# 21_GPIOs_EXP.net
KiCad netlist of a schematic drawn in Altium Designer
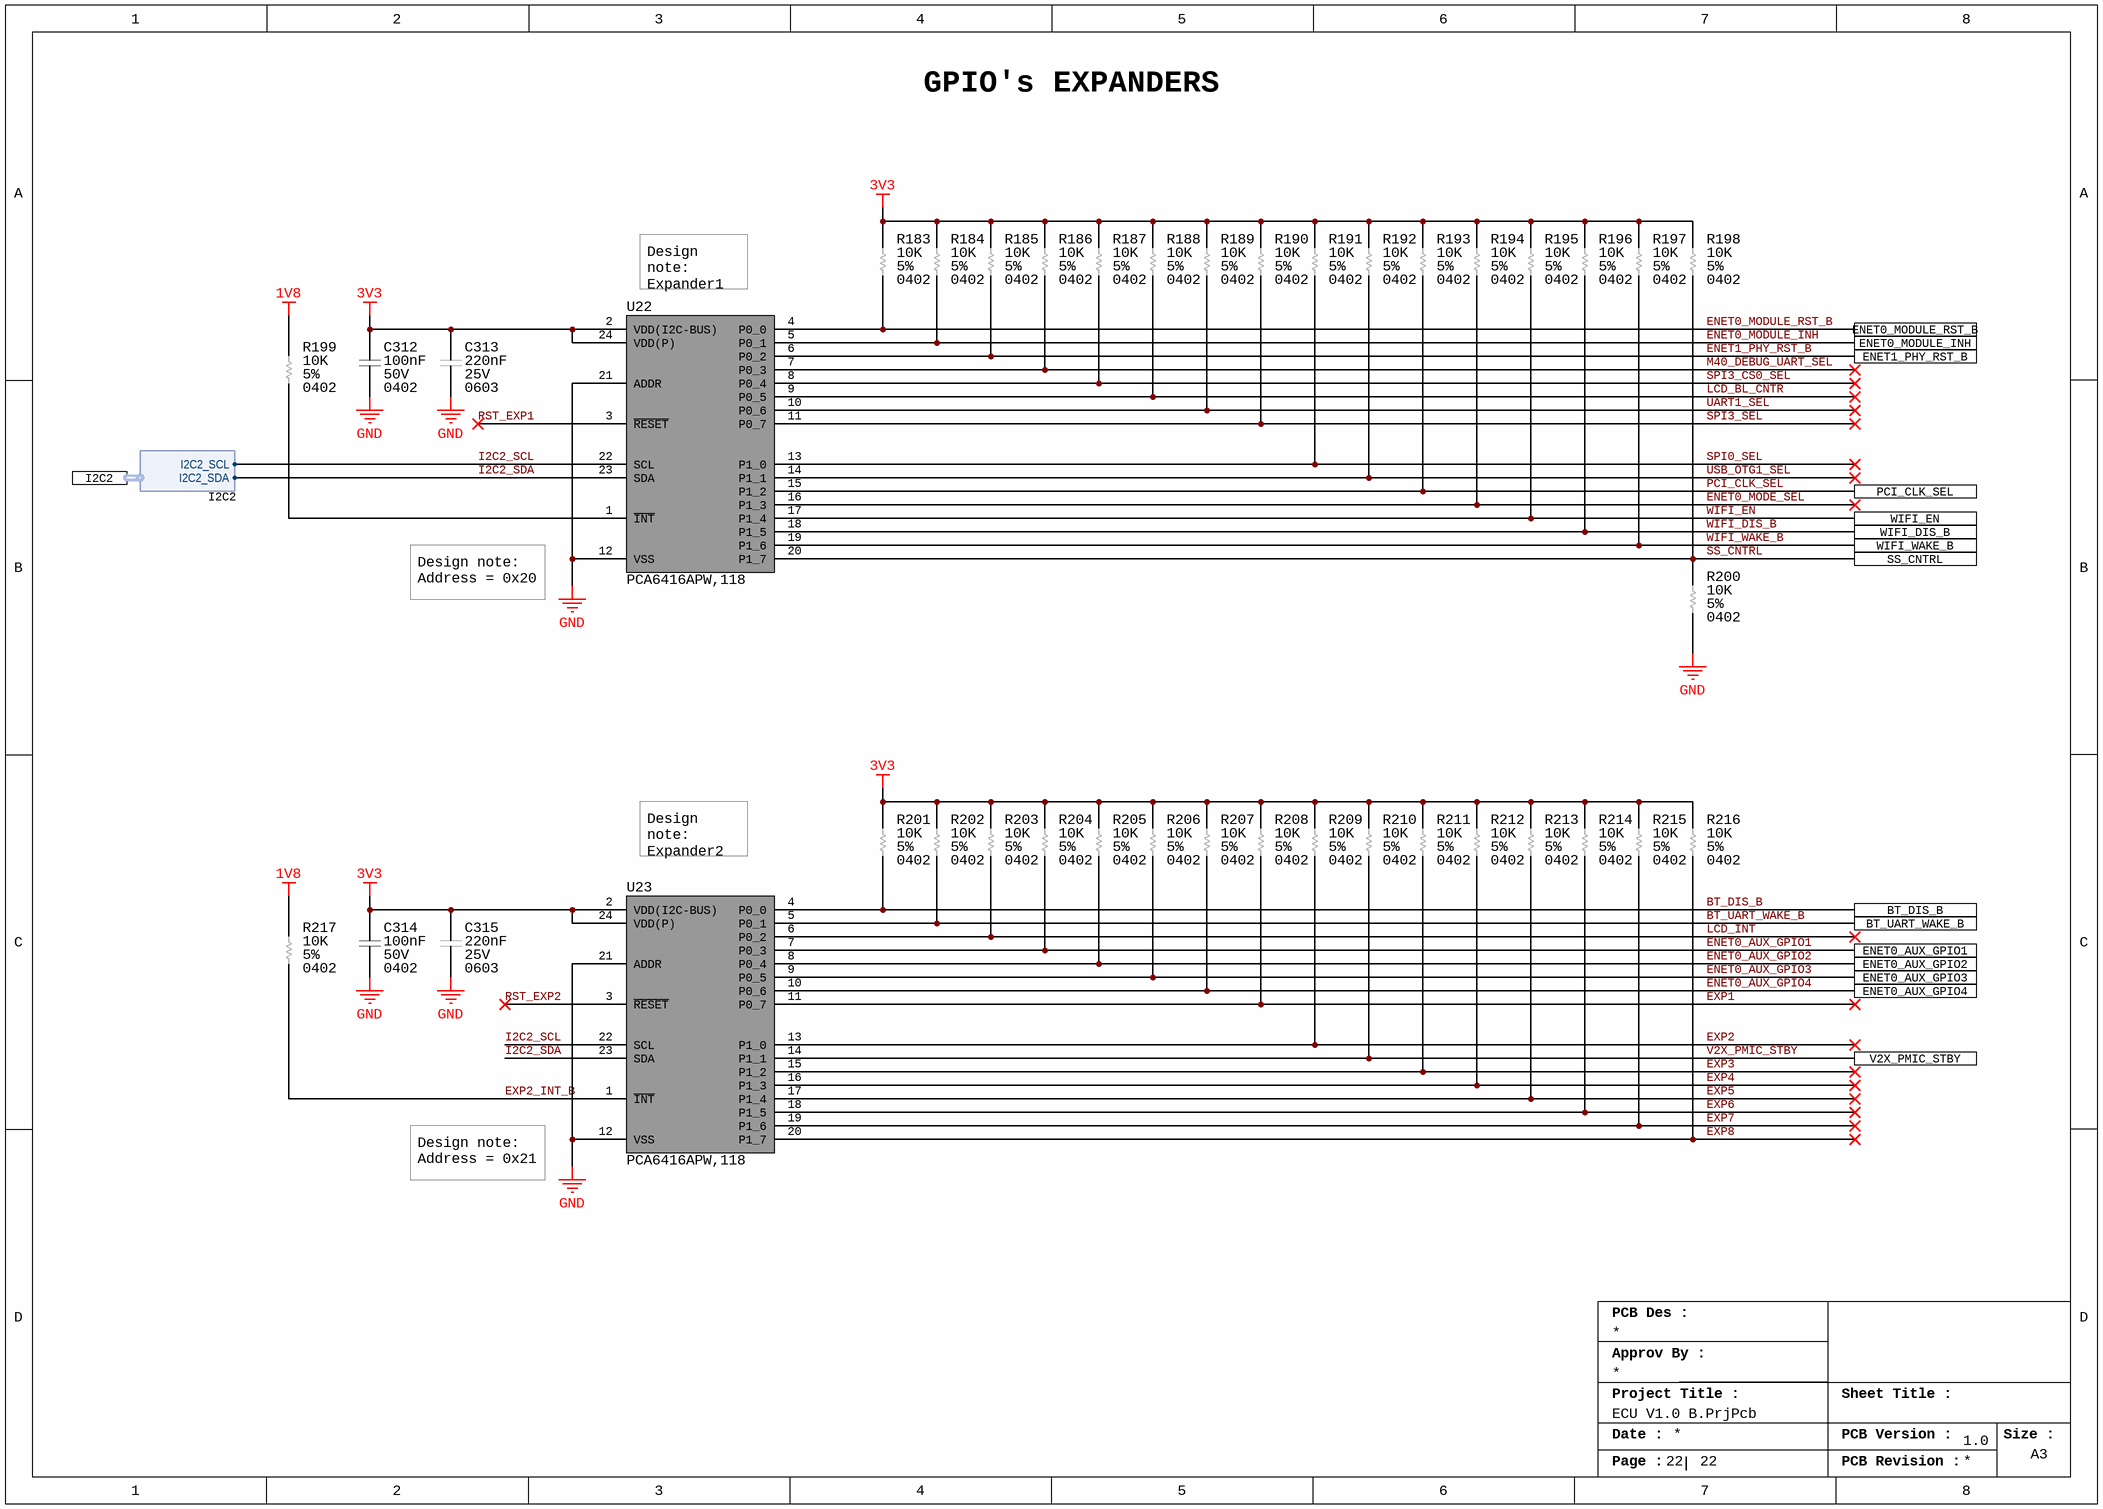
[diagram p0: 21_GPIOs_EXP.SchDoc]

(export (version "E")
  (design (tool "Eeschema 10.0.6"))
  (components
    (comp (ref "C312")
      (value "GRM155R71H104KE14D")
      (footprint "CAP_0402_CAPC1005X05N")
      (description "Multilayer Ceramic Capacitor, 0.1 uF, 16 V, ± 10%, X7R, 0402 [1005 Metric]")
      (fields
        (field (name "MANUFACTURER") "Murata")
        (field (name "TOLERANCE") "10%")
        (field (name "VOLTAGE RATING") "50V")
        (field (name "CAPACITANCE") "100nF")
        (field (name "CASE/PACKAGE") "0402")
      )
      (libsource (lib "Electronic Devices_LIB") (part "CAP_100NF_50V_X7R_0402"))
    )
    (comp (ref "C313")
      (value "GRM188R71E224KA88D")
      (footprint "CAP_0603_CAPC1608X08N")
      (description "Multilayer Ceramic Capacitor, 0.22 uF, 25 V, ± 10%, X7R, 0603 [1608 Metric]")
      (fields
        (field (name "MANUFACTURER") "Murata")
        (field (name "TOLERANCE") "10%")
        (field (name "CASE/PACKAGE") "0603")
        (field (name "VOLTAGE RATING") "25V")
        (field (name "CAPACITANCE") "220nF")
      )
      (libsource (lib "Electronic Devices_LIB") (part "CAP_0.22uF_25V_X7R_0603"))
    )
    (comp (ref "C314")
      (value "GRM155R71H104KE14D")
      (footprint "CAP_0402_CAPC1005X05N")
      (description "Multilayer Ceramic Capacitor, 0.1 uF, 16 V, ± 10%, X7R, 0402 [1005 Metric]")
      (fields
        (field (name "MANUFACTURER") "Murata")
        (field (name "TOLERANCE") "10%")
        (field (name "VOLTAGE RATING") "50V")
        (field (name "CAPACITANCE") "100nF")
        (field (name "CASE/PACKAGE") "0402")
      )
      (libsource (lib "Electronic Devices_LIB") (part "CAP_100NF_50V_X7R_0402"))
    )
    (comp (ref "C315")
      (value "GRM188R71E224KA88D")
      (footprint "CAP_0603_CAPC1608X08N")
      (description "Multilayer Ceramic Capacitor, 0.22 uF, 25 V, ± 10%, X7R, 0603 [1608 Metric]")
      (fields
        (field (name "MANUFACTURER") "Murata")
        (field (name "TOLERANCE") "10%")
        (field (name "CASE/PACKAGE") "0603")
        (field (name "VOLTAGE RATING") "25V")
        (field (name "CAPACITANCE") "220nF")
      )
      (libsource (lib "Electronic Devices_LIB") (part "CAP_0.22uF_25V_X7R_0603"))
    )
    (comp (ref "R183")
      (value "ERJ-2GEJ103X")
      (footprint "RES_0402_RESC1005X04N")
      (description "Res Thick Film 0402 10K Ohm 5% 1/10W ±200ppm/°C Molded SMD Punched Carrier T/R")
      (fields
        (field (name "MANUFACTURER") "Panasonic")
        (field (name "TOLERANCE") "5%")
        (field (name "RESISTANCE") "10K")
        (field (name "CASE/PACKAGE") "0402")
      )
      (libsource (lib "Electronic Devices_LIB") (part "RES_10K_5%_100mW_0402"))
    )
    (comp (ref "R184")
      (value "ERJ-2GEJ103X")
      (footprint "RES_0402_RESC1005X04N")
      (description "Res Thick Film 0402 10K Ohm 5% 1/10W ±200ppm/°C Molded SMD Punched Carrier T/R")
      (fields
        (field (name "MANUFACTURER") "Panasonic")
        (field (name "TOLERANCE") "5%")
        (field (name "RESISTANCE") "10K")
        (field (name "CASE/PACKAGE") "0402")
      )
      (libsource (lib "Electronic Devices_LIB") (part "RES_10K_5%_100mW_0402"))
    )
    (comp (ref "R185")
      (value "ERJ-2GEJ103X")
      (footprint "RES_0402_RESC1005X04N")
      (description "Res Thick Film 0402 10K Ohm 5% 1/10W ±200ppm/°C Molded SMD Punched Carrier T/R")
      (fields
        (field (name "MANUFACTURER") "Panasonic")
        (field (name "TOLERANCE") "5%")
        (field (name "RESISTANCE") "10K")
        (field (name "CASE/PACKAGE") "0402")
      )
      (libsource (lib "Electronic Devices_LIB") (part "RES_10K_5%_100mW_0402"))
    )
    (comp (ref "R186")
      (value "ERJ-2GEJ103X")
      (footprint "RES_0402_RESC1005X04N")
      (description "Res Thick Film 0402 10K Ohm 5% 1/10W ±200ppm/°C Molded SMD Punched Carrier T/R")
      (fields
        (field (name "MANUFACTURER") "Panasonic")
        (field (name "TOLERANCE") "5%")
        (field (name "RESISTANCE") "10K")
        (field (name "CASE/PACKAGE") "0402")
      )
      (libsource (lib "Electronic Devices_LIB") (part "RES_10K_5%_100mW_0402"))
    )
    (comp (ref "R187")
      (value "ERJ-2GEJ103X")
      (footprint "RES_0402_RESC1005X04N")
      (description "Res Thick Film 0402 10K Ohm 5% 1/10W ±200ppm/°C Molded SMD Punched Carrier T/R")
      (fields
        (field (name "MANUFACTURER") "Panasonic")
        (field (name "TOLERANCE") "5%")
        (field (name "RESISTANCE") "10K")
        (field (name "CASE/PACKAGE") "0402")
      )
      (libsource (lib "Electronic Devices_LIB") (part "RES_10K_5%_100mW_0402"))
    )
    (comp (ref "R188")
      (value "ERJ-2GEJ103X")
      (footprint "RES_0402_RESC1005X04N")
      (description "Res Thick Film 0402 10K Ohm 5% 1/10W ±200ppm/°C Molded SMD Punched Carrier T/R")
      (fields
        (field (name "MANUFACTURER") "Panasonic")
        (field (name "TOLERANCE") "5%")
        (field (name "RESISTANCE") "10K")
        (field (name "CASE/PACKAGE") "0402")
      )
      (libsource (lib "Electronic Devices_LIB") (part "RES_10K_5%_100mW_0402"))
    )
    (comp (ref "R189")
      (value "ERJ-2GEJ103X")
      (footprint "RES_0402_RESC1005X04N")
      (description "Res Thick Film 0402 10K Ohm 5% 1/10W ±200ppm/°C Molded SMD Punched Carrier T/R")
      (fields
        (field (name "MANUFACTURER") "Panasonic")
        (field (name "TOLERANCE") "5%")
        (field (name "RESISTANCE") "10K")
        (field (name "CASE/PACKAGE") "0402")
      )
      (libsource (lib "Electronic Devices_LIB") (part "RES_10K_5%_100mW_0402"))
    )
    (comp (ref "R190")
      (value "ERJ-2GEJ103X")
      (footprint "RES_0402_RESC1005X04N")
      (description "Res Thick Film 0402 10K Ohm 5% 1/10W ±200ppm/°C Molded SMD Punched Carrier T/R")
      (fields
        (field (name "MANUFACTURER") "Panasonic")
        (field (name "TOLERANCE") "5%")
        (field (name "RESISTANCE") "10K")
        (field (name "CASE/PACKAGE") "0402")
      )
      (libsource (lib "Electronic Devices_LIB") (part "RES_10K_5%_100mW_0402"))
    )
    (comp (ref "R191")
      (value "ERJ-2GEJ103X")
      (footprint "RES_0402_RESC1005X04N")
      (description "Res Thick Film 0402 10K Ohm 5% 1/10W ±200ppm/°C Molded SMD Punched Carrier T/R")
      (fields
        (field (name "MANUFACTURER") "Panasonic")
        (field (name "TOLERANCE") "5%")
        (field (name "RESISTANCE") "10K")
        (field (name "CASE/PACKAGE") "0402")
      )
      (libsource (lib "Electronic Devices_LIB") (part "RES_10K_5%_100mW_0402"))
    )
    (comp (ref "R192")
      (value "ERJ-2GEJ103X")
      (footprint "RES_0402_RESC1005X04N")
      (description "Res Thick Film 0402 10K Ohm 5% 1/10W ±200ppm/°C Molded SMD Punched Carrier T/R")
      (fields
        (field (name "MANUFACTURER") "Panasonic")
        (field (name "TOLERANCE") "5%")
        (field (name "RESISTANCE") "10K")
        (field (name "CASE/PACKAGE") "0402")
      )
      (libsource (lib "Electronic Devices_LIB") (part "RES_10K_5%_100mW_0402"))
    )
    (comp (ref "R193")
      (value "ERJ-2GEJ103X")
      (footprint "RES_0402_RESC1005X04N")
      (description "Res Thick Film 0402 10K Ohm 5% 1/10W ±200ppm/°C Molded SMD Punched Carrier T/R")
      (fields
        (field (name "MANUFACTURER") "Panasonic")
        (field (name "TOLERANCE") "5%")
        (field (name "RESISTANCE") "10K")
        (field (name "CASE/PACKAGE") "0402")
      )
      (libsource (lib "Electronic Devices_LIB") (part "RES_10K_5%_100mW_0402"))
    )
    (comp (ref "R194")
      (value "ERJ-2GEJ103X")
      (footprint "RES_0402_RESC1005X04N")
      (description "Res Thick Film 0402 10K Ohm 5% 1/10W ±200ppm/°C Molded SMD Punched Carrier T/R")
      (fields
        (field (name "MANUFACTURER") "Panasonic")
        (field (name "TOLERANCE") "5%")
        (field (name "RESISTANCE") "10K")
        (field (name "CASE/PACKAGE") "0402")
      )
      (libsource (lib "Electronic Devices_LIB") (part "RES_10K_5%_100mW_0402"))
    )
    (comp (ref "R195")
      (value "ERJ-2GEJ103X")
      (footprint "RES_0402_RESC1005X04N")
      (description "Res Thick Film 0402 10K Ohm 5% 1/10W ±200ppm/°C Molded SMD Punched Carrier T/R")
      (fields
        (field (name "MANUFACTURER") "Panasonic")
        (field (name "TOLERANCE") "5%")
        (field (name "RESISTANCE") "10K")
        (field (name "CASE/PACKAGE") "0402")
      )
      (libsource (lib "Electronic Devices_LIB") (part "RES_10K_5%_100mW_0402"))
    )
    (comp (ref "R196")
      (value "ERJ-2GEJ103X")
      (footprint "RES_0402_RESC1005X04N")
      (description "Res Thick Film 0402 10K Ohm 5% 1/10W ±200ppm/°C Molded SMD Punched Carrier T/R")
      (fields
        (field (name "MANUFACTURER") "Panasonic")
        (field (name "TOLERANCE") "5%")
        (field (name "RESISTANCE") "10K")
        (field (name "CASE/PACKAGE") "0402")
      )
      (libsource (lib "Electronic Devices_LIB") (part "RES_10K_5%_100mW_0402"))
    )
    (comp (ref "R197")
      (value "ERJ-2GEJ103X")
      (footprint "RES_0402_RESC1005X04N")
      (description "Res Thick Film 0402 10K Ohm 5% 1/10W ±200ppm/°C Molded SMD Punched Carrier T/R")
      (fields
        (field (name "MANUFACTURER") "Panasonic")
        (field (name "TOLERANCE") "5%")
        (field (name "RESISTANCE") "10K")
        (field (name "CASE/PACKAGE") "0402")
      )
      (libsource (lib "Electronic Devices_LIB") (part "RES_10K_5%_100mW_0402"))
    )
    (comp (ref "R198")
      (value "ERJ-2GEJ103X")
      (footprint "RES_0402_RESC1005X04N")
      (description "Res Thick Film 0402 10K Ohm 5% 1/10W ±200ppm/°C Molded SMD Punched Carrier T/R")
      (fields
        (field (name "MANUFACTURER") "Panasonic")
        (field (name "TOLERANCE") "5%")
        (field (name "RESISTANCE") "10K")
        (field (name "CASE/PACKAGE") "0402")
      )
      (libsource (lib "Electronic Devices_LIB") (part "RES_10K_5%_100mW_0402"))
    )
    (comp (ref "R199")
      (value "ERJ-2GEJ103X")
      (footprint "RES_0402_RESC1005X04N")
      (description "Res Thick Film 0402 10K Ohm 5% 1/10W ±200ppm/°C Molded SMD Punched Carrier T/R")
      (fields
        (field (name "MANUFACTURER") "Panasonic")
        (field (name "TOLERANCE") "5%")
        (field (name "RESISTANCE") "10K")
        (field (name "CASE/PACKAGE") "0402")
      )
      (libsource (lib "Electronic Devices_LIB") (part "RES_10K_5%_100mW_0402"))
    )
    (comp (ref "R200")
      (value "ERJ-2GEJ103X")
      (footprint "RES_0402_RESC1005X04N")
      (description "Res Thick Film 0402 10K Ohm 5% 1/10W ±200ppm/°C Molded SMD Punched Carrier T/R")
      (fields
        (field (name "MANUFACTURER") "Panasonic")
        (field (name "TOLERANCE") "5%")
        (field (name "RESISTANCE") "10K")
        (field (name "CASE/PACKAGE") "0402")
      )
      (libsource (lib "Electronic Devices_LIB") (part "RES_10K_5%_100mW_0402"))
    )
    (comp (ref "R201")
      (value "ERJ-2GEJ103X")
      (footprint "RES_0402_RESC1005X04N")
      (description "Res Thick Film 0402 10K Ohm 5% 1/10W ±200ppm/°C Molded SMD Punched Carrier T/R")
      (fields
        (field (name "MANUFACTURER") "Panasonic")
        (field (name "TOLERANCE") "5%")
        (field (name "RESISTANCE") "10K")
        (field (name "CASE/PACKAGE") "0402")
      )
      (libsource (lib "Electronic Devices_LIB") (part "RES_10K_5%_100mW_0402"))
    )
    (comp (ref "R202")
      (value "ERJ-2GEJ103X")
      (footprint "RES_0402_RESC1005X04N")
      (description "Res Thick Film 0402 10K Ohm 5% 1/10W ±200ppm/°C Molded SMD Punched Carrier T/R")
      (fields
        (field (name "MANUFACTURER") "Panasonic")
        (field (name "TOLERANCE") "5%")
        (field (name "RESISTANCE") "10K")
        (field (name "CASE/PACKAGE") "0402")
      )
      (libsource (lib "Electronic Devices_LIB") (part "RES_10K_5%_100mW_0402"))
    )
    (comp (ref "R203")
      (value "ERJ-2GEJ103X")
      (footprint "RES_0402_RESC1005X04N")
      (description "Res Thick Film 0402 10K Ohm 5% 1/10W ±200ppm/°C Molded SMD Punched Carrier T/R")
      (fields
        (field (name "MANUFACTURER") "Panasonic")
        (field (name "TOLERANCE") "5%")
        (field (name "RESISTANCE") "10K")
        (field (name "CASE/PACKAGE") "0402")
      )
      (libsource (lib "Electronic Devices_LIB") (part "RES_10K_5%_100mW_0402"))
    )
    (comp (ref "R204")
      (value "ERJ-2GEJ103X")
      (footprint "RES_0402_RESC1005X04N")
      (description "Res Thick Film 0402 10K Ohm 5% 1/10W ±200ppm/°C Molded SMD Punched Carrier T/R")
      (fields
        (field (name "MANUFACTURER") "Panasonic")
        (field (name "TOLERANCE") "5%")
        (field (name "RESISTANCE") "10K")
        (field (name "CASE/PACKAGE") "0402")
      )
      (libsource (lib "Electronic Devices_LIB") (part "RES_10K_5%_100mW_0402"))
    )
    (comp (ref "R205")
      (value "ERJ-2GEJ103X")
      (footprint "RES_0402_RESC1005X04N")
      (description "Res Thick Film 0402 10K Ohm 5% 1/10W ±200ppm/°C Molded SMD Punched Carrier T/R")
      (fields
        (field (name "MANUFACTURER") "Panasonic")
        (field (name "TOLERANCE") "5%")
        (field (name "RESISTANCE") "10K")
        (field (name "CASE/PACKAGE") "0402")
      )
      (libsource (lib "Electronic Devices_LIB") (part "RES_10K_5%_100mW_0402"))
    )
    (comp (ref "R206")
      (value "ERJ-2GEJ103X")
      (footprint "RES_0402_RESC1005X04N")
      (description "Res Thick Film 0402 10K Ohm 5% 1/10W ±200ppm/°C Molded SMD Punched Carrier T/R")
      (fields
        (field (name "MANUFACTURER") "Panasonic")
        (field (name "TOLERANCE") "5%")
        (field (name "RESISTANCE") "10K")
        (field (name "CASE/PACKAGE") "0402")
      )
      (libsource (lib "Electronic Devices_LIB") (part "RES_10K_5%_100mW_0402"))
    )
    (comp (ref "R207")
      (value "ERJ-2GEJ103X")
      (footprint "RES_0402_RESC1005X04N")
      (description "Res Thick Film 0402 10K Ohm 5% 1/10W ±200ppm/°C Molded SMD Punched Carrier T/R")
      (fields
        (field (name "MANUFACTURER") "Panasonic")
        (field (name "TOLERANCE") "5%")
        (field (name "RESISTANCE") "10K")
        (field (name "CASE/PACKAGE") "0402")
      )
      (libsource (lib "Electronic Devices_LIB") (part "RES_10K_5%_100mW_0402"))
    )
    (comp (ref "R208")
      (value "ERJ-2GEJ103X")
      (footprint "RES_0402_RESC1005X04N")
      (description "Res Thick Film 0402 10K Ohm 5% 1/10W ±200ppm/°C Molded SMD Punched Carrier T/R")
      (fields
        (field (name "MANUFACTURER") "Panasonic")
        (field (name "TOLERANCE") "5%")
        (field (name "RESISTANCE") "10K")
        (field (name "CASE/PACKAGE") "0402")
      )
      (libsource (lib "Electronic Devices_LIB") (part "RES_10K_5%_100mW_0402"))
    )
    (comp (ref "R209")
      (value "ERJ-2GEJ103X")
      (footprint "RES_0402_RESC1005X04N")
      (description "Res Thick Film 0402 10K Ohm 5% 1/10W ±200ppm/°C Molded SMD Punched Carrier T/R")
      (fields
        (field (name "MANUFACTURER") "Panasonic")
        (field (name "TOLERANCE") "5%")
        (field (name "RESISTANCE") "10K")
        (field (name "CASE/PACKAGE") "0402")
      )
      (libsource (lib "Electronic Devices_LIB") (part "RES_10K_5%_100mW_0402"))
    )
    (comp (ref "R210")
      (value "ERJ-2GEJ103X")
      (footprint "RES_0402_RESC1005X04N")
      (description "Res Thick Film 0402 10K Ohm 5% 1/10W ±200ppm/°C Molded SMD Punched Carrier T/R")
      (fields
        (field (name "MANUFACTURER") "Panasonic")
        (field (name "TOLERANCE") "5%")
        (field (name "RESISTANCE") "10K")
        (field (name "CASE/PACKAGE") "0402")
      )
      (libsource (lib "Electronic Devices_LIB") (part "RES_10K_5%_100mW_0402"))
    )
    (comp (ref "R211")
      (value "ERJ-2GEJ103X")
      (footprint "RES_0402_RESC1005X04N")
      (description "Res Thick Film 0402 10K Ohm 5% 1/10W ±200ppm/°C Molded SMD Punched Carrier T/R")
      (fields
        (field (name "MANUFACTURER") "Panasonic")
        (field (name "TOLERANCE") "5%")
        (field (name "RESISTANCE") "10K")
        (field (name "CASE/PACKAGE") "0402")
      )
      (libsource (lib "Electronic Devices_LIB") (part "RES_10K_5%_100mW_0402"))
    )
    (comp (ref "R212")
      (value "ERJ-2GEJ103X")
      (footprint "RES_0402_RESC1005X04N")
      (description "Res Thick Film 0402 10K Ohm 5% 1/10W ±200ppm/°C Molded SMD Punched Carrier T/R")
      (fields
        (field (name "MANUFACTURER") "Panasonic")
        (field (name "TOLERANCE") "5%")
        (field (name "RESISTANCE") "10K")
        (field (name "CASE/PACKAGE") "0402")
      )
      (libsource (lib "Electronic Devices_LIB") (part "RES_10K_5%_100mW_0402"))
    )
    (comp (ref "R213")
      (value "ERJ-2GEJ103X")
      (footprint "RES_0402_RESC1005X04N")
      (description "Res Thick Film 0402 10K Ohm 5% 1/10W ±200ppm/°C Molded SMD Punched Carrier T/R")
      (fields
        (field (name "MANUFACTURER") "Panasonic")
        (field (name "TOLERANCE") "5%")
        (field (name "RESISTANCE") "10K")
        (field (name "CASE/PACKAGE") "0402")
      )
      (libsource (lib "Electronic Devices_LIB") (part "RES_10K_5%_100mW_0402"))
    )
    (comp (ref "R214")
      (value "ERJ-2GEJ103X")
      (footprint "RES_0402_RESC1005X04N")
      (description "Res Thick Film 0402 10K Ohm 5% 1/10W ±200ppm/°C Molded SMD Punched Carrier T/R")
      (fields
        (field (name "MANUFACTURER") "Panasonic")
        (field (name "TOLERANCE") "5%")
        (field (name "RESISTANCE") "10K")
        (field (name "CASE/PACKAGE") "0402")
      )
      (libsource (lib "Electronic Devices_LIB") (part "RES_10K_5%_100mW_0402"))
    )
    (comp (ref "R215")
      (value "ERJ-2GEJ103X")
      (footprint "RES_0402_RESC1005X04N")
      (description "Res Thick Film 0402 10K Ohm 5% 1/10W ±200ppm/°C Molded SMD Punched Carrier T/R")
      (fields
        (field (name "MANUFACTURER") "Panasonic")
        (field (name "TOLERANCE") "5%")
        (field (name "RESISTANCE") "10K")
        (field (name "CASE/PACKAGE") "0402")
      )
      (libsource (lib "Electronic Devices_LIB") (part "RES_10K_5%_100mW_0402"))
    )
    (comp (ref "R216")
      (value "ERJ-2GEJ103X")
      (footprint "RES_0402_RESC1005X04N")
      (description "Res Thick Film 0402 10K Ohm 5% 1/10W ±200ppm/°C Molded SMD Punched Carrier T/R")
      (fields
        (field (name "MANUFACTURER") "Panasonic")
        (field (name "TOLERANCE") "5%")
        (field (name "RESISTANCE") "10K")
        (field (name "CASE/PACKAGE") "0402")
      )
      (libsource (lib "Electronic Devices_LIB") (part "RES_10K_5%_100mW_0402"))
    )
    (comp (ref "R217")
      (value "ERJ-2GEJ103X")
      (footprint "RES_0402_RESC1005X04N")
      (description "Res Thick Film 0402 10K Ohm 5% 1/10W ±200ppm/°C Molded SMD Punched Carrier T/R")
      (fields
        (field (name "MANUFACTURER") "Panasonic")
        (field (name "TOLERANCE") "5%")
        (field (name "RESISTANCE") "10K")
        (field (name "CASE/PACKAGE") "0402")
      )
      (libsource (lib "Electronic Devices_LIB") (part "RES_10K_5%_100mW_0402"))
    )
    (comp (ref "U22")
      (value "PCA6416APW,118")
      (footprint "PCA6416APW118")
      (description "I2C/SMBus Interface 100kHz/400kHz 5.5V 24-Pin TSSOP T/R")
      (fields (field (name "MANUFACTURER") "NXP Semiconductors"))
      (libsource (lib "Electronic Devices_LIB") (part "IC_EXPANDER_16_PCA6416APW,118"))
    )
    (comp (ref "U23")
      (value "PCA6416APW,118")
      (footprint "PCA6416APW118")
      (description "I2C/SMBus Interface 100kHz/400kHz 5.5V 24-Pin TSSOP T/R")
      (fields (field (name "MANUFACTURER") "NXP Semiconductors"))
      (libsource (lib "Electronic Devices_LIB") (part "IC_EXPANDER_16_PCA6416APW,118"))
    )
  )
  (nets
    (net (code "2") (name "/BT_DIS_B") (class "Default")
      (node (ref "R201") (pin "1") (pinfunction "1_1") (pintype "passive"))
      (node (ref "U23") (pin "4") (pinfunction "P0_0_4") (pintype "passive"))
    )
    (net (code "3") (name "/BT_UART_WAKE_B") (class "Default")
      (node (ref "R202") (pin "1") (pinfunction "1_1") (pintype "passive"))
      (node (ref "U23") (pin "5") (pinfunction "P0_1_5") (pintype "passive"))
    )
    (net (code "4") (name "/ENET0_AUX_GPIO1") (class "Default")
      (node (ref "R204") (pin "1") (pinfunction "1_1") (pintype "passive"))
      (node (ref "U23") (pin "7") (pinfunction "P0_3_7") (pintype "passive"))
    )
    (net (code "5") (name "/ENET0_AUX_GPIO2") (class "Default")
      (node (ref "R205") (pin "1") (pinfunction "1_1") (pintype "passive"))
      (node (ref "U23") (pin "8") (pinfunction "P0_4_8") (pintype "passive"))
    )
    (net (code "6") (name "/ENET0_AUX_GPIO3") (class "Default")
      (node (ref "R206") (pin "1") (pinfunction "1_1") (pintype "passive"))
      (node (ref "U23") (pin "9") (pinfunction "P0_5_9") (pintype "passive"))
    )
    (net (code "7") (name "/ENET0_AUX_GPIO4") (class "Default")
      (node (ref "R207") (pin "1") (pinfunction "1_1") (pintype "passive"))
      (node (ref "U23") (pin "10") (pinfunction "P0_6_10") (pintype "passive"))
    )
    (net (code "8") (name "/ENET0_MODE_SEL") (class "Default")
      (node (ref "R194") (pin "1") (pinfunction "1_1") (pintype "passive"))
      (node (ref "U22") (pin "16") (pinfunction "P1_3_16") (pintype "passive"))
    )
    (net (code "9") (name "/ENET0_MODULE_INH") (class "Default")
      (node (ref "R184") (pin "1") (pinfunction "1_1") (pintype "passive"))
      (node (ref "U22") (pin "5") (pinfunction "P0_1_5") (pintype "passive"))
    )
    (net (code "10") (name "/ENET0_MODULE_RST_B") (class "Default")
      (node (ref "R183") (pin "1") (pinfunction "1_1") (pintype "passive"))
      (node (ref "U22") (pin "4") (pinfunction "P0_0_4") (pintype "passive"))
    )
    (net (code "11") (name "/ENET1_PHY_RST_B") (class "Default")
      (node (ref "R185") (pin "1") (pinfunction "1_1") (pintype "passive"))
      (node (ref "U22") (pin "6") (pinfunction "P0_2_6") (pintype "passive"))
    )
    (net (code "12") (name "/EXP1") (class "Default")
      (node (ref "R208") (pin "1") (pinfunction "1_1") (pintype "passive"))
      (node (ref "U23") (pin "11") (pinfunction "P0_7_11") (pintype "passive"))
    )
    (net (code "13") (name "/EXP2") (class "Default")
      (node (ref "R209") (pin "1") (pinfunction "1_1") (pintype "passive"))
      (node (ref "U23") (pin "13") (pinfunction "P1_0_13") (pintype "passive"))
    )
    (net (code "14") (name "/EXP2_INT_B") (class "Default")
      (node (ref "R217") (pin "1") (pinfunction "1_1") (pintype "passive"))
      (node (ref "U23") (pin "1") (pinfunction "~{INT}_1") (pintype "passive"))
    )
    (net (code "15") (name "/EXP3") (class "Default")
      (node (ref "R211") (pin "1") (pinfunction "1_1") (pintype "passive"))
      (node (ref "U23") (pin "15") (pinfunction "P1_2_15") (pintype "passive"))
    )
    (net (code "16") (name "/EXP4") (class "Default")
      (node (ref "R212") (pin "1") (pinfunction "1_1") (pintype "passive"))
      (node (ref "U23") (pin "16") (pinfunction "P1_3_16") (pintype "passive"))
    )
    (net (code "17") (name "/EXP5") (class "Default")
      (node (ref "R213") (pin "1") (pinfunction "1_1") (pintype "passive"))
      (node (ref "U23") (pin "17") (pinfunction "P1_4_17") (pintype "passive"))
    )
    (net (code "18") (name "/EXP6") (class "Default")
      (node (ref "R214") (pin "1") (pinfunction "1_1") (pintype "passive"))
      (node (ref "U23") (pin "18") (pinfunction "P1_5_18") (pintype "passive"))
    )
    (net (code "19") (name "/EXP7") (class "Default")
      (node (ref "R215") (pin "1") (pinfunction "1_1") (pintype "passive"))
      (node (ref "U23") (pin "19") (pinfunction "P1_6_19") (pintype "passive"))
    )
    (net (code "20") (name "/EXP8") (class "Default")
      (node (ref "R216") (pin "1") (pinfunction "1_1") (pintype "passive"))
      (node (ref "U23") (pin "20") (pinfunction "P1_7_20") (pintype "passive"))
    )
    (net (code "21") (name "/I2C2_SCL") (class "Default")
      (node (ref "U22") (pin "22") (pinfunction "SCL_22") (pintype "passive"))
      (node (ref "U23") (pin "22") (pinfunction "SCL_22") (pintype "passive"))
    )
    (net (code "22") (name "/I2C2_SDA") (class "Default")
      (node (ref "U22") (pin "23") (pinfunction "SDA_23") (pintype "passive"))
      (node (ref "U23") (pin "23") (pinfunction "SDA_23") (pintype "passive"))
    )
    (net (code "23") (name "/LCD_BL_CNTR") (class "Default")
      (node (ref "R188") (pin "1") (pinfunction "1_1") (pintype "passive"))
      (node (ref "U22") (pin "9") (pinfunction "P0_5_9") (pintype "passive"))
    )
    (net (code "24") (name "/LCD_INT") (class "Default")
      (node (ref "R203") (pin "1") (pinfunction "1_1") (pintype "passive"))
      (node (ref "U23") (pin "6") (pinfunction "P0_2_6") (pintype "passive"))
    )
    (net (code "25") (name "/M40_DEBUG_UART_SEL") (class "Default")
      (node (ref "R186") (pin "1") (pinfunction "1_1") (pintype "passive"))
      (node (ref "U22") (pin "7") (pinfunction "P0_3_7") (pintype "passive"))
    )
    (net (code "26") (name "/PCI_CLK_SEL") (class "Default")
      (node (ref "R193") (pin "1") (pinfunction "1_1") (pintype "passive"))
      (node (ref "U22") (pin "15") (pinfunction "P1_2_15") (pintype "passive"))
    )
    (net (code "27") (name "/RST_EXP1") (class "Default")
      (node (ref "U22") (pin "3") (pinfunction "~{RESET}_3") (pintype "passive+no_connect"))
    )
    (net (code "28") (name "/RST_EXP2") (class "Default")
      (node (ref "U23") (pin "3") (pinfunction "~{RESET}_3") (pintype "passive+no_connect"))
    )
    (net (code "29") (name "/SPI0_SEL") (class "Default")
      (node (ref "R191") (pin "1") (pinfunction "1_1") (pintype "passive"))
      (node (ref "U22") (pin "13") (pinfunction "P1_0_13") (pintype "passive"))
    )
    (net (code "30") (name "/SPI3_CS0_SEL") (class "Default")
      (node (ref "R187") (pin "1") (pinfunction "1_1") (pintype "passive"))
      (node (ref "U22") (pin "8") (pinfunction "P0_4_8") (pintype "passive"))
    )
    (net (code "31") (name "/SPI3_SEL") (class "Default")
      (node (ref "R190") (pin "1") (pinfunction "1_1") (pintype "passive"))
      (node (ref "U22") (pin "11") (pinfunction "P0_7_11") (pintype "passive"))
    )
    (net (code "32") (name "/SS_CNTRL") (class "Default")
      (node (ref "R198") (pin "1") (pinfunction "1_1") (pintype "passive"))
      (node (ref "R200") (pin "2") (pinfunction "2_2") (pintype "passive"))
      (node (ref "U22") (pin "20") (pinfunction "P1_7_20") (pintype "passive"))
    )
    (net (code "33") (name "/UART1_SEL") (class "Default")
      (node (ref "R189") (pin "1") (pinfunction "1_1") (pintype "passive"))
      (node (ref "U22") (pin "10") (pinfunction "P0_6_10") (pintype "passive"))
    )
    (net (code "34") (name "/USB_OTG1_SEL") (class "Default")
      (node (ref "R192") (pin "1") (pinfunction "1_1") (pintype "passive"))
      (node (ref "U22") (pin "14") (pinfunction "P1_1_14") (pintype "passive"))
    )
    (net (code "35") (name "/V2X_PMIC_STBY") (class "Default")
      (node (ref "R210") (pin "1") (pinfunction "1_1") (pintype "passive"))
      (node (ref "U23") (pin "14") (pinfunction "P1_1_14") (pintype "passive"))
    )
    (net (code "36") (name "/WIFI_DIS_B") (class "Default")
      (node (ref "R196") (pin "1") (pinfunction "1_1") (pintype "passive"))
      (node (ref "U22") (pin "18") (pinfunction "P1_5_18") (pintype "passive"))
    )
    (net (code "37") (name "/WIFI_EN") (class "Default")
      (node (ref "R195") (pin "1") (pinfunction "1_1") (pintype "passive"))
      (node (ref "U22") (pin "17") (pinfunction "P1_4_17") (pintype "passive"))
    )
    (net (code "38") (name "/WIFI_WAKE_B") (class "Default")
      (node (ref "R197") (pin "1") (pinfunction "1_1") (pintype "passive"))
      (node (ref "U22") (pin "19") (pinfunction "P1_6_19") (pintype "passive"))
    )
    (net (code "40") (name "1V8") (class "Default")
      (node (ref "R199") (pin "2") (pinfunction "2_2") (pintype "passive"))
      (node (ref "R217") (pin "2") (pinfunction "2_2") (pintype "passive"))
    )
    (net (code "41") (name "3V3") (class "Default")
      (node (ref "C312") (pin "2") (pinfunction "2_2") (pintype "passive"))
      (node (ref "C313") (pin "2") (pinfunction "2_2") (pintype "passive"))
      (node (ref "C314") (pin "2") (pinfunction "2_2") (pintype "passive"))
      (node (ref "C315") (pin "2") (pinfunction "2_2") (pintype "passive"))
      (node (ref "R183") (pin "2") (pinfunction "2_2") (pintype "passive"))
      (node (ref "R184") (pin "2") (pinfunction "2_2") (pintype "passive"))
      (node (ref "R185") (pin "2") (pinfunction "2_2") (pintype "passive"))
      (node (ref "R186") (pin "2") (pinfunction "2_2") (pintype "passive"))
      (node (ref "R187") (pin "2") (pinfunction "2_2") (pintype "passive"))
      (node (ref "R188") (pin "2") (pinfunction "2_2") (pintype "passive"))
      (node (ref "R189") (pin "2") (pinfunction "2_2") (pintype "passive"))
      (node (ref "R190") (pin "2") (pinfunction "2_2") (pintype "passive"))
      (node (ref "R191") (pin "2") (pinfunction "2_2") (pintype "passive"))
      (node (ref "R192") (pin "2") (pinfunction "2_2") (pintype "passive"))
      (node (ref "R193") (pin "2") (pinfunction "2_2") (pintype "passive"))
      (node (ref "R194") (pin "2") (pinfunction "2_2") (pintype "passive"))
      (node (ref "R195") (pin "2") (pinfunction "2_2") (pintype "passive"))
      (node (ref "R196") (pin "2") (pinfunction "2_2") (pintype "passive"))
      (node (ref "R197") (pin "2") (pinfunction "2_2") (pintype "passive"))
      (node (ref "R198") (pin "2") (pinfunction "2_2") (pintype "passive"))
      (node (ref "R201") (pin "2") (pinfunction "2_2") (pintype "passive"))
      (node (ref "R202") (pin "2") (pinfunction "2_2") (pintype "passive"))
      (node (ref "R203") (pin "2") (pinfunction "2_2") (pintype "passive"))
      (node (ref "R204") (pin "2") (pinfunction "2_2") (pintype "passive"))
      (node (ref "R205") (pin "2") (pinfunction "2_2") (pintype "passive"))
      (node (ref "R206") (pin "2") (pinfunction "2_2") (pintype "passive"))
      (node (ref "R207") (pin "2") (pinfunction "2_2") (pintype "passive"))
      (node (ref "R208") (pin "2") (pinfunction "2_2") (pintype "passive"))
      (node (ref "R209") (pin "2") (pinfunction "2_2") (pintype "passive"))
      (node (ref "R210") (pin "2") (pinfunction "2_2") (pintype "passive"))
      (node (ref "R211") (pin "2") (pinfunction "2_2") (pintype "passive"))
      (node (ref "R212") (pin "2") (pinfunction "2_2") (pintype "passive"))
      (node (ref "R213") (pin "2") (pinfunction "2_2") (pintype "passive"))
      (node (ref "R214") (pin "2") (pinfunction "2_2") (pintype "passive"))
      (node (ref "R215") (pin "2") (pinfunction "2_2") (pintype "passive"))
      (node (ref "R216") (pin "2") (pinfunction "2_2") (pintype "passive"))
      (node (ref "U22") (pin "2") (pinfunction "VDD(I2C-BUS)_2") (pintype "passive"))
      (node (ref "U22") (pin "24") (pinfunction "VDD(P)_24") (pintype "passive"))
      (node (ref "U23") (pin "2") (pinfunction "VDD(I2C-BUS)_2") (pintype "passive"))
      (node (ref "U23") (pin "24") (pinfunction "VDD(P)_24") (pintype "passive"))
    )
    (net (code "42") (name "GND") (class "Default")
      (node (ref "C312") (pin "1") (pinfunction "1_1") (pintype "passive"))
      (node (ref "C313") (pin "1") (pinfunction "1_1") (pintype "passive"))
      (node (ref "C314") (pin "1") (pinfunction "1_1") (pintype "passive"))
      (node (ref "C315") (pin "1") (pinfunction "1_1") (pintype "passive"))
      (node (ref "R200") (pin "1") (pinfunction "1_1") (pintype "passive"))
      (node (ref "U22") (pin "12") (pinfunction "VSS_12") (pintype "passive"))
      (node (ref "U22") (pin "21") (pinfunction "ADDR_21") (pintype "passive"))
      (node (ref "U23") (pin "12") (pinfunction "VSS_12") (pintype "passive"))
      (node (ref "U23") (pin "21") (pinfunction "ADDR_21") (pintype "passive"))
    )
    (net (code "43") (name "Net-(U22-~{INT})") (class "Default")
      (node (ref "R199") (pin "1") (pinfunction "1_1") (pintype "passive"))
      (node (ref "U22") (pin "1") (pinfunction "~{INT}_1") (pintype "passive"))
    )
  )
)
